# 02_CPU_STM32F103C8T6.net
KiCad netlist of a schematic drawn in Altium Designer
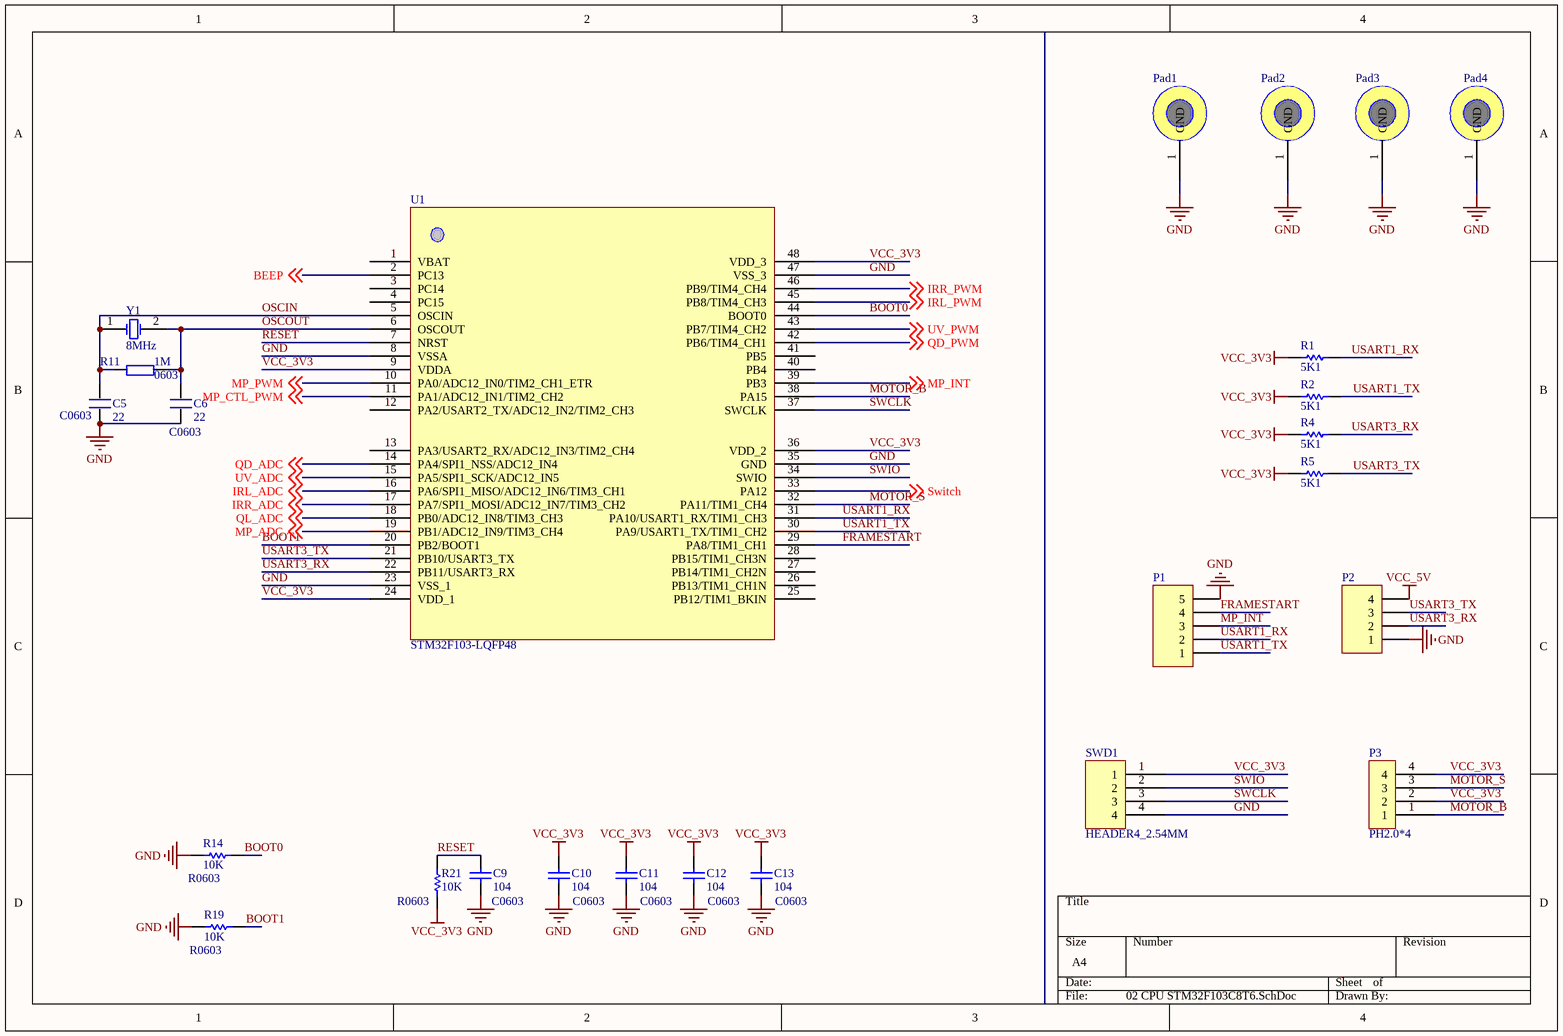
[diagram p0: 02 CPU STM32F103C8T6.SchDoc]

(export (version "E")
  (design (tool "Eeschema 10.0.6"))
  (components
    (comp (ref "C5") (value "22") (footprint "C0603") (libsource (lib "Explorer STM32F407封装库") (part "C")))
    (comp (ref "C6") (value "22") (footprint "C0603") (libsource (lib "Explorer STM32F407封装库") (part "C")))
    (comp (ref "C9")
      (value "104")
      (footprint "C0603")
      (description "Capacitor")
      (fields (field (name "PUBLISHER") "Altium Limited"))
      (libsource (lib "") (part "Cap_1"))
    )
    (comp (ref "C10")
      (value "104")
      (footprint "C0603")
      (description "Capacitor")
      (fields
        (field (name "MANUFACTURER") "Generic Components")
        (field (name "PUBLISHER") "Altium Hobart Technology Centre")
      )
      (libsource (lib "Miscellaneous Devices") (part "Cap"))
    )
    (comp (ref "C11")
      (value "104")
      (footprint "C0603")
      (description "Capacitor")
      (fields
        (field (name "MANUFACTURER") "Generic Components")
        (field (name "PUBLISHER") "Altium Hobart Technology Centre")
      )
      (libsource (lib "Miscellaneous Devices") (part "Cap"))
    )
    (comp (ref "C12")
      (value "104")
      (footprint "C0603")
      (description "Capacitor")
      (fields
        (field (name "MANUFACTURER") "Generic Components")
        (field (name "PUBLISHER") "Altium Hobart Technology Centre")
      )
      (libsource (lib "Miscellaneous Devices") (part "Cap"))
    )
    (comp (ref "C13")
      (value "104")
      (footprint "C0603")
      (description "Capacitor")
      (fields
        (field (name "MANUFACTURER") "Generic Components")
        (field (name "PUBLISHER") "Altium Hobart Technology Centre")
      )
      (libsource (lib "Miscellaneous Devices") (part "Cap"))
    )
    (comp (ref "P1")
      (value "~")
      (footprint "PH2.0*5")
      (description "Header, 5-Pin")
      (fields (field (name "PUBLISHER") "Altium Limited"))
      (libsource (lib "Miscellaneous Connectors") (part "Header 5"))
    )
    (comp (ref "P2")
      (value "~")
      (footprint "PH2.0*4")
      (description "Header, 4-Pin")
      (fields (field (name "PUBLISHER") "Altium Limited"))
      (libsource (lib "Miscellaneous Connectors") (part "Header 4"))
    )
    (comp (ref "P3")
      (value "PH2.0*4")
      (footprint "PH2.0*4")
      (libsource (lib "Integrated_Library") (part "PH2.0*4"))
    )
    (comp (ref "Pad1")
      (value "PAD_3.3(6.8)")
      (footprint "PAD_3.3(6.8)")
      (libsource (lib "Integrated_Library") (part "PAD_3.3(6.8)"))
    )
    (comp (ref "Pad2")
      (value "PAD_3.3(6.8)")
      (footprint "PAD_3.3(6.8)")
      (libsource (lib "Integrated_Library") (part "PAD_3.3(6.8)"))
    )
    (comp (ref "Pad3")
      (value "PAD_3.3(6.8)")
      (footprint "PAD_3.3(6.8)")
      (libsource (lib "Integrated_Library") (part "PAD_3.3(6.8)"))
    )
    (comp (ref "Pad4")
      (value "PAD_3.3(6.8)")
      (footprint "PAD_3.3(6.8)")
      (libsource (lib "Integrated_Library") (part "PAD_3.3(6.8)"))
    )
    (comp (ref "R1")
      (value "5K1")
      (footprint "R0603")
      (description "Resistor")
      (fields
        (field (name "MANUFACTURER") "Generic Components")
        (field (name "PUBLISHER") "Altium Hobart Technology Centre")
      )
      (libsource (lib "Miscellaneous Devices") (part "Res1"))
    )
    (comp (ref "R2")
      (value "5K1")
      (footprint "R0603")
      (description "Resistor")
      (fields
        (field (name "MANUFACTURER") "Generic Components")
        (field (name "PUBLISHER") "Altium Hobart Technology Centre")
      )
      (libsource (lib "Miscellaneous Devices") (part "Res1"))
    )
    (comp (ref "R4")
      (value "5K1")
      (footprint "R0603")
      (description "Resistor")
      (fields
        (field (name "MANUFACTURER") "Generic Components")
        (field (name "PUBLISHER") "Altium Hobart Technology Centre")
      )
      (libsource (lib "Miscellaneous Devices") (part "Res1"))
    )
    (comp (ref "R5")
      (value "5K1")
      (footprint "R0603")
      (description "Resistor")
      (fields
        (field (name "MANUFACTURER") "Generic Components")
        (field (name "PUBLISHER") "Altium Hobart Technology Centre")
      )
      (libsource (lib "Miscellaneous Devices") (part "Res1"))
    )
    (comp (ref "R11") (value "1M") (footprint "0603") (libsource (lib "Explorer STM32F407封装库") (part "R")))
    (comp (ref "R14")
      (value "10K")
      (footprint "R0603")
      (description "Semiconductor Resistor")
      (fields (field (name "PUBLISHER") "Altium Limited"))
      (libsource (lib "Miscellaneous Devices") (part "Res Semi"))
    )
    (comp (ref "R19")
      (value "10K")
      (footprint "R0603")
      (description "Semiconductor Resistor")
      (fields (field (name "PUBLISHER") "Altium Limited"))
      (libsource (lib "Miscellaneous Devices") (part "Res Semi"))
    )
    (comp (ref "R21")
      (value "10K")
      (footprint "R0603")
      (description "Semiconductor Resistor")
      (fields (field (name "PUBLISHER") "Altium Limited"))
      (libsource (lib "Miscellaneous Devices") (part "Res Semi"))
    )
    (comp (ref "SWD1")
      (value "HEADER4_2.54MM")
      (footprint "HEADER4_2.54MM")
      (libsource (lib "Integrated_Library") (part "HEADER4_2.54MM"))
    )
    (comp (ref "U1")
      (value "STM32F103-LQFP48")
      (footprint "STM32F103_48P")
      (libsource (lib "Integrated_Library") (part "STM32F103-LQFP48"))
    )
    (comp (ref "Y1")
      (value "8MHz")
      (footprint "XTAL8M")
      (description "Crystal Oscillator")
      (fields (field (name "PUBLISHER") "Altium Limited"))
      (libsource (lib "Explorer STM32F407封装库") (part "XTAL"))
    )
  )
  (nets
    (net (code "1") (name "/BOOT0") (class "Default")
      (node (ref "R14") (pin "2") (pinfunction "2_2") (pintype "passive"))
      (node (ref "U1") (pin "44") (pinfunction "BOOT0_44") (pintype "passive"))
    )
    (net (code "2") (name "/BOOT1") (class "Default")
      (node (ref "R19") (pin "2") (pinfunction "2_2") (pintype "passive"))
      (node (ref "U1") (pin "20") (pinfunction "PB2/BOOT1_20") (pintype "passive"))
    )
    (net (code "3") (name "/FRAMESTART") (class "Default")
      (node (ref "P1") (pin "4") (pinfunction "4_4") (pintype "passive"))
      (node (ref "U1") (pin "29") (pinfunction "PA8/TIM1_CH1_29") (pintype "passive"))
    )
    (net (code "4") (name "/MOTOR_B") (class "Default")
      (node (ref "P3") (pin "1") (pinfunction "1_1") (pintype "passive"))
      (node (ref "U1") (pin "38") (pinfunction "PA15_38") (pintype "passive"))
    )
    (net (code "5") (name "/MOTOR_S") (class "Default")
      (node (ref "P3") (pin "3") (pinfunction "3_3") (pintype "passive"))
      (node (ref "U1") (pin "32") (pinfunction "PA11/TIM1_CH4_32") (pintype "passive"))
    )
    (net (code "6") (name "/OSCIN") (class "Default")
      (node (ref "C5") (pin "2") (pintype "passive"))
      (node (ref "R11") (pin "1") (pintype "passive"))
      (node (ref "U1") (pin "5") (pinfunction "OSCIN_5") (pintype "passive"))
      (node (ref "Y1") (pin "1") (pinfunction "OSC1_1") (pintype "passive"))
    )
    (net (code "7") (name "/OSCOUT") (class "Default")
      (node (ref "C6") (pin "2") (pintype "passive"))
      (node (ref "R11") (pin "2") (pintype "passive"))
      (node (ref "U1") (pin "6") (pinfunction "OSCOUT_6") (pintype "passive"))
      (node (ref "Y1") (pin "2") (pinfunction "OSC2_2") (pintype "passive"))
    )
    (net (code "8") (name "/RESET") (class "Default")
      (node (ref "C9") (pin "1") (pinfunction "1_1") (pintype "passive"))
      (node (ref "R21") (pin "2") (pinfunction "2_2") (pintype "passive"))
      (node (ref "U1") (pin "7") (pinfunction "NRST_7") (pintype "passive"))
    )
    (net (code "9") (name "/SWCLK") (class "Default")
      (node (ref "SWD1") (pin "3") (pinfunction "3_3") (pintype "passive"))
      (node (ref "U1") (pin "37") (pinfunction "SWCLK_37") (pintype "passive"))
    )
    (net (code "10") (name "/SWIO") (class "Default")
      (node (ref "SWD1") (pin "2") (pinfunction "2_2") (pintype "passive"))
      (node (ref "U1") (pin "34") (pinfunction "SWIO_34") (pintype "passive"))
    )
    (net (code "11") (name "/USART1_RX") (class "Default")
      (node (ref "P1") (pin "2") (pinfunction "2_2") (pintype "passive"))
      (node (ref "R1") (pin "2") (pinfunction "2_2") (pintype "passive"))
      (node (ref "U1") (pin "31") (pinfunction "PA10/USART1_RX/TIM1_CH3_31") (pintype "passive"))
    )
    (net (code "12") (name "/USART1_TX") (class "Default")
      (node (ref "P1") (pin "1") (pinfunction "1_1") (pintype "passive"))
      (node (ref "R2") (pin "2") (pinfunction "2_2") (pintype "passive"))
      (node (ref "U1") (pin "30") (pinfunction "PA9/USART1_TX/TIM1_CH2_30") (pintype "passive"))
    )
    (net (code "13") (name "/USART3_RX") (class "Default")
      (node (ref "P2") (pin "2") (pinfunction "2_2") (pintype "passive"))
      (node (ref "R4") (pin "2") (pinfunction "2_2") (pintype "passive"))
      (node (ref "U1") (pin "22") (pinfunction "PB11/USART3_RX_22") (pintype "passive"))
    )
    (net (code "14") (name "/USART3_TX") (class "Default")
      (node (ref "P2") (pin "3") (pinfunction "3_3") (pintype "passive"))
      (node (ref "R5") (pin "2") (pinfunction "2_2") (pintype "passive"))
      (node (ref "U1") (pin "21") (pinfunction "PB10/USART3_TX_21") (pintype "passive"))
    )
    (net (code "15") (name "BEEP") (class "Default")
      (node (ref "U1") (pin "2") (pinfunction "PC13_2") (pintype "passive"))
    )
    (net (code "16") (name "GND") (class "Default")
      (node (ref "C10") (pin "2") (pinfunction "2_2") (pintype "passive"))
      (node (ref "C11") (pin "2") (pinfunction "2_2") (pintype "passive"))
      (node (ref "C12") (pin "2") (pinfunction "2_2") (pintype "passive"))
      (node (ref "C13") (pin "2") (pinfunction "2_2") (pintype "passive"))
      (node (ref "C5") (pin "1") (pintype "passive"))
      (node (ref "C6") (pin "1") (pintype "passive"))
      (node (ref "C9") (pin "2") (pinfunction "2_2") (pintype "passive"))
      (node (ref "P1") (pin "5") (pinfunction "5_5") (pintype "passive"))
      (node (ref "P2") (pin "1") (pinfunction "1_1") (pintype "passive"))
      (node (ref "Pad1") (pin "1") (pinfunction "GND_1") (pintype "passive"))
      (node (ref "Pad2") (pin "1") (pinfunction "GND_1") (pintype "passive"))
      (node (ref "Pad3") (pin "1") (pinfunction "GND_1") (pintype "passive"))
      (node (ref "Pad4") (pin "1") (pinfunction "GND_1") (pintype "passive"))
      (node (ref "R14") (pin "1") (pinfunction "1_1") (pintype "passive"))
      (node (ref "R19") (pin "1") (pinfunction "1_1") (pintype "passive"))
      (node (ref "SWD1") (pin "4") (pinfunction "4_4") (pintype "passive"))
      (node (ref "U1") (pin "23") (pinfunction "VSS_1_23") (pintype "passive"))
      (node (ref "U1") (pin "35") (pinfunction "GND_35") (pintype "passive"))
      (node (ref "U1") (pin "47") (pinfunction "VSS_3_47") (pintype "passive"))
      (node (ref "U1") (pin "8") (pinfunction "VSSA_8") (pintype "passive"))
    )
    (net (code "17") (name "IRL_ADC") (class "Default")
      (node (ref "U1") (pin "16") (pinfunction "PA6/SPI1_MISO/ADC12_IN6/TIM3_CH1_16") (pintype "passive"))
    )
    (net (code "18") (name "IRL_PWM") (class "Default")
      (node (ref "U1") (pin "45") (pinfunction "PB8/TIM4_CH3_45") (pintype "passive"))
    )
    (net (code "19") (name "IRR_ADC") (class "Default")
      (node (ref "U1") (pin "17") (pinfunction "PA7/SPI1_MOSI/ADC12_IN7/TIM3_CH2_17") (pintype "passive"))
    )
    (net (code "20") (name "IRR_PWM") (class "Default")
      (node (ref "U1") (pin "46") (pinfunction "PB9/TIM4_CH4_46") (pintype "passive"))
    )
    (net (code "21") (name "MP_ADC") (class "Default")
      (node (ref "U1") (pin "19") (pinfunction "PB1/ADC12_IN9/TIM3_CH4_19") (pintype "passive"))
    )
    (net (code "22") (name "MP_CTL_PWM") (class "Default")
      (node (ref "U1") (pin "11") (pinfunction "PA1/ADC12_IN1/TIM2_CH2_11") (pintype "passive"))
    )
    (net (code "23") (name "MP_INT") (class "Default")
      (node (ref "P1") (pin "3") (pinfunction "3_3") (pintype "passive"))
      (node (ref "U1") (pin "39") (pinfunction "PB3_39") (pintype "passive"))
    )
    (net (code "24") (name "MP_PWM") (class "Default")
      (node (ref "U1") (pin "10") (pinfunction "PA0/ADC12_IN0/TIM2_CH1_ETR_10") (pintype "passive"))
    )
    (net (code "25") (name "QD_ADC") (class "Default")
      (node (ref "U1") (pin "14") (pinfunction "PA4/SPI1_NSS/ADC12_IN4_14") (pintype "passive"))
    )
    (net (code "26") (name "QD_PWM") (class "Default")
      (node (ref "U1") (pin "42") (pinfunction "PB6/TIM4_CH1_42") (pintype "passive"))
    )
    (net (code "27") (name "QL_ADC") (class "Default")
      (node (ref "U1") (pin "18") (pinfunction "PB0/ADC12_IN8/TIM3_CH3_18") (pintype "passive"))
    )
    (net (code "28") (name "Switch") (class "Default")
      (node (ref "U1") (pin "33") (pinfunction "PA12_33") (pintype "passive"))
    )
    (net (code "29") (name "UV_ADC") (class "Default")
      (node (ref "U1") (pin "15") (pinfunction "PA5/SPI1_SCK/ADC12_IN5_15") (pintype "passive"))
    )
    (net (code "30") (name "UV_PWM") (class "Default")
      (node (ref "U1") (pin "43") (pinfunction "PB7/TIM4_CH2_43") (pintype "passive"))
    )
    (net (code "31") (name "VCC_3V3") (class "Default")
      (node (ref "C10") (pin "1") (pinfunction "1_1") (pintype "passive"))
      (node (ref "C11") (pin "1") (pinfunction "1_1") (pintype "passive"))
      (node (ref "C12") (pin "1") (pinfunction "1_1") (pintype "passive"))
      (node (ref "C13") (pin "1") (pinfunction "1_1") (pintype "passive"))
      (node (ref "P3") (pin "2") (pinfunction "2_2") (pintype "passive"))
      (node (ref "P3") (pin "4") (pinfunction "4_4") (pintype "passive"))
      (node (ref "R1") (pin "1") (pinfunction "1_1") (pintype "passive"))
      (node (ref "R2") (pin "1") (pinfunction "1_1") (pintype "passive"))
      (node (ref "R21") (pin "1") (pinfunction "1_1") (pintype "passive"))
      (node (ref "R4") (pin "1") (pinfunction "1_1") (pintype "passive"))
      (node (ref "R5") (pin "1") (pinfunction "1_1") (pintype "passive"))
      (node (ref "SWD1") (pin "1") (pinfunction "1_1") (pintype "passive"))
      (node (ref "U1") (pin "24") (pinfunction "VDD_1_24") (pintype "passive"))
      (node (ref "U1") (pin "36") (pinfunction "VDD_2_36") (pintype "passive"))
      (node (ref "U1") (pin "48") (pinfunction "VDD_3_48") (pintype "passive"))
      (node (ref "U1") (pin "9") (pinfunction "VDDA_9") (pintype "passive"))
    )
    (net (code "32") (name "VCC_5V") (class "Default")
      (node (ref "P2") (pin "4") (pinfunction "4_4") (pintype "passive"))
    )
    (net (code "33") (name "unconnected-(U1-PA2{slash}USART2_TX{slash}ADC12_IN2{slash}TIM2_CH3-Pad12)") (class "Default")
      (node (ref "U1") (pin "12") (pinfunction "PA2/USART2_TX/ADC12_IN2/TIM2_CH3_12") (pintype "passive"))
    )
    (net (code "34") (name "unconnected-(U1-PA3{slash}USART2_RX{slash}ADC12_IN3{slash}TIM2_CH4-Pad13)") (class "Default")
      (node (ref "U1") (pin "13") (pinfunction "PA3/USART2_RX/ADC12_IN3/TIM2_CH4_13") (pintype "passive"))
    )
    (net (code "35") (name "unconnected-(U1-PB4-Pad40)") (class "Default")
      (node (ref "U1") (pin "40") (pinfunction "PB4_40") (pintype "passive"))
    )
    (net (code "36") (name "unconnected-(U1-PB5-Pad41)") (class "Default")
      (node (ref "U1") (pin "41") (pinfunction "PB5_41") (pintype "passive"))
    )
    (net (code "37") (name "unconnected-(U1-PB12{slash}TIM1_BKIN-Pad25)") (class "Default")
      (node (ref "U1") (pin "25") (pinfunction "PB12/TIM1_BKIN_25") (pintype "passive"))
    )
    (net (code "38") (name "unconnected-(U1-PB13{slash}TIM1_CH1N-Pad26)") (class "Default")
      (node (ref "U1") (pin "26") (pinfunction "PB13/TIM1_CH1N_26") (pintype "passive"))
    )
    (net (code "39") (name "unconnected-(U1-PB14{slash}TIM1_CH2N-Pad27)") (class "Default")
      (node (ref "U1") (pin "27") (pinfunction "PB14/TIM1_CH2N_27") (pintype "passive"))
    )
    (net (code "40") (name "unconnected-(U1-PB15{slash}TIM1_CH3N-Pad28)") (class "Default")
      (node (ref "U1") (pin "28") (pinfunction "PB15/TIM1_CH3N_28") (pintype "passive"))
    )
    (net (code "41") (name "unconnected-(U1-PC14-Pad3)") (class "Default")
      (node (ref "U1") (pin "3") (pinfunction "PC14_3") (pintype "passive"))
    )
    (net (code "42") (name "unconnected-(U1-PC15-Pad4)") (class "Default")
      (node (ref "U1") (pin "4") (pinfunction "PC15_4") (pintype "passive"))
    )
    (net (code "43") (name "unconnected-(U1-VBAT-Pad1)") (class "Default")
      (node (ref "U1") (pin "1") (pinfunction "VBAT_1") (pintype "passive"))
    )
  )
)
